# TMC2209_Camera_Slider_PCB.net
KiCad netlist of a schematic drawn in EAGLE
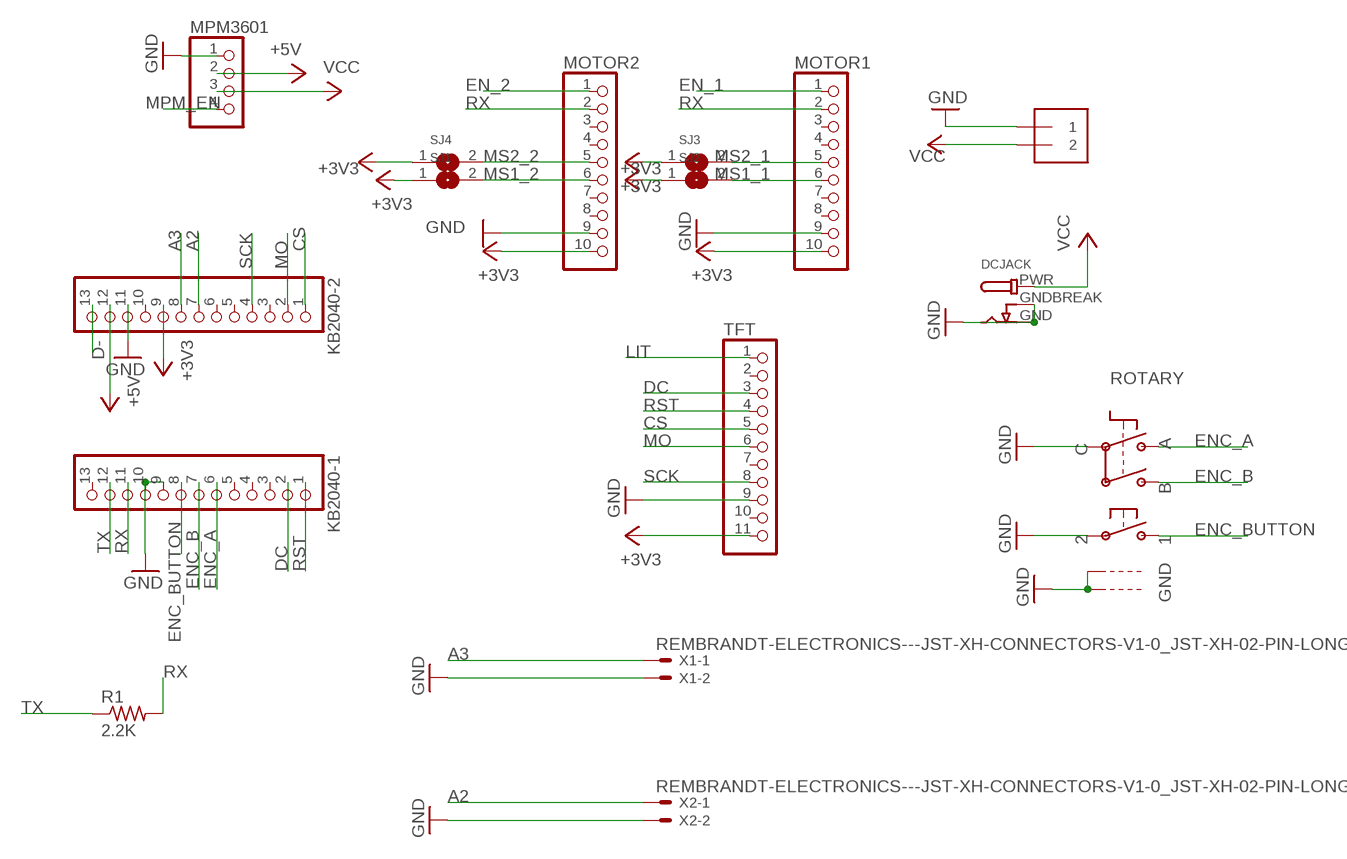
[diagram p0: schematic, sheet 1]

(export (version "E")
  (design (tool "Eeschema 10.0.6"))
  (components
    (comp (ref "DCJACK")
      (value "DCBARRELPTH")
      (footprint "eagle-import:DCJACK_2MM_PTH")
      (libsource (lib "eagle-import") (part "DCBARRELPTH"))
    )
    (comp (ref "J1")
      (value "1X2-3.5MM")
      (footprint "eagle-import:1X2-3.5MM")
      (libsource (lib "eagle-import") (part "1X2-3.5MM"))
    )
    (comp (ref "KB2040-1")
      (value "HEADER-1X13")
      (footprint "eagle-import:1X13_ROUND_70")
      (libsource (lib "eagle-import") (part "HEADER-1X13"))
    )
    (comp (ref "KB2040-2")
      (value "HEADER-1X13")
      (footprint "eagle-import:1X13_ROUND_70")
      (libsource (lib "eagle-import") (part "HEADER-1X13"))
    )
    (comp (ref "MOTOR1")
      (value "HEADER-1X10")
      (footprint "eagle-import:1X10_OVAL")
      (libsource (lib "eagle-import") (part "HEADER-1X10"))
    )
    (comp (ref "MOTOR2")
      (value "HEADER-1X10")
      (footprint "eagle-import:1X10_OVAL")
      (libsource (lib "eagle-import") (part "HEADER-1X10"))
    )
    (comp (ref "MPM3601")
      (value "HEADER-1X4")
      (footprint "eagle-import:1X04_OVAL")
      (libsource (lib "eagle-import") (part "HEADER-1X4"))
    )
    (comp (ref "R1")
      (value "2.2K")
      (footprint "eagle-import:0309_12")
      (libsource (lib "eagle-import") (part "R-US_0309/12"))
    )
    (comp (ref "ROTARY")
      (value "ENCODER_PLUS_SWITCH_BOURNS_PEC11")
      (footprint "eagle-import:PEC11+SWITCH")
      (libsource (lib "eagle-import") (part "ENCODER_PLUS_SWITCH_PEC11_BOURNS"))
    )
    (comp (ref "SJ1")
      (value "SOLDERJUMPERCLOSED")
      (footprint "eagle-import:SOLDERJUMPER_CLOSEDWIRE")
      (libsource (lib "eagle-import") (part "SOLDERJUMPERCLOSED"))
    )
    (comp (ref "SJ2")
      (value "SOLDERJUMPERREFLOW")
      (footprint "eagle-import:SOLDERJUMPER_REFLOW")
      (libsource (lib "eagle-import") (part "SOLDERJUMPERREFLOW"))
    )
    (comp (ref "SJ3")
      (value "SOLDERJUMPERREFLOW")
      (footprint "eagle-import:SOLDERJUMPER_REFLOW")
      (libsource (lib "eagle-import") (part "SOLDERJUMPERREFLOW"))
    )
    (comp (ref "SJ4")
      (value "SOLDERJUMPERREFLOW")
      (footprint "eagle-import:SOLDERJUMPER_REFLOW")
      (libsource (lib "eagle-import") (part "SOLDERJUMPERREFLOW"))
    )
    (comp (ref "TFT")
      (value "HEADER-1X11")
      (footprint "eagle-import:1X11_ROUND")
      (libsource (lib "eagle-import") (part "HEADER-1X11"))
    )
    (comp (ref "X1")
      (value "REMBRANDT-ELECTRONICS---JST-XH-CONNECTORS-V1-0_JST-XH-02-PIN-LONG-PAD")
      (footprint "eagle-import:REMBRANDT-ELECTRONICS---JST-XH-CONNECTORS-V1-0_JST-XH-02-PACKAGE-LONG-PAD")
      (libsource (lib "eagle-import") (part "REMBRANDT-ELECTRONICS---JST-XH-CONNECTORS-V1-0_JST-XH-02-PIN-LONG-PAD"))
    )
    (comp (ref "X2")
      (value "REMBRANDT-ELECTRONICS---JST-XH-CONNECTORS-V1-0_JST-XH-02-PIN-LONG-PAD")
      (footprint "eagle-import:REMBRANDT-ELECTRONICS---JST-XH-CONNECTORS-V1-0_JST-XH-02-PACKAGE-LONG-PAD")
      (libsource (lib "eagle-import") (part "REMBRANDT-ELECTRONICS---JST-XH-CONNECTORS-V1-0_JST-XH-02-PIN-LONG-PAD"))
    )
  )
  (nets
    (net (code "1") (name "+3V3") (class "Default")
      (node (ref "KB2040-2") (pin "9") (pinfunction "9_9") (pintype "passive"))
      (node (ref "MOTOR1") (pin "10") (pinfunction "10_10") (pintype "passive"))
      (node (ref "MOTOR2") (pin "10") (pinfunction "10_10") (pintype "passive"))
      (node (ref "SJ1") (pin "1") (pinfunction "1_1") (pintype "passive"))
      (node (ref "SJ2") (pin "1") (pinfunction "1_1") (pintype "passive"))
      (node (ref "SJ3") (pin "1") (pinfunction "1_1") (pintype "passive"))
      (node (ref "SJ4") (pin "1") (pinfunction "1_1") (pintype "passive"))
      (node (ref "TFT") (pin "11") (pinfunction "11_11") (pintype "passive"))
    )
    (net (code "2") (name "+5V") (class "Default")
      (node (ref "KB2040-2") (pin "12") (pinfunction "12_12") (pintype "passive"))
      (node (ref "MPM3601") (pin "2") (pinfunction "2_2") (pintype "passive"))
    )
    (net (code "3") (name "/A2") (class "Default")
      (node (ref "KB2040-2") (pin "7") (pinfunction "7_7") (pintype "passive"))
      (node (ref "X2") (pin "1") (pinfunction "S_1") (pintype "passive"))
    )
    (net (code "4") (name "/A3") (class "Default")
      (node (ref "KB2040-2") (pin "8") (pinfunction "8_8") (pintype "passive"))
      (node (ref "X1") (pin "1") (pinfunction "S_1") (pintype "passive"))
    )
    (net (code "5") (name "/CS") (class "Default")
      (node (ref "KB2040-2") (pin "1") (pinfunction "1_1") (pintype "passive"))
      (node (ref "TFT") (pin "5") (pinfunction "5_5") (pintype "passive"))
    )
    (net (code "6") (name "/D-") (class "Default")
      (node (ref "KB2040-2") (pin "13") (pinfunction "13_13") (pintype "passive"))
    )
    (net (code "7") (name "/DC") (class "Default")
      (node (ref "KB2040-1") (pin "2") (pinfunction "2_2") (pintype "passive"))
      (node (ref "TFT") (pin "3") (pinfunction "3_3") (pintype "passive"))
    )
    (net (code "8") (name "/ENC_A") (class "Default")
      (node (ref "KB2040-1") (pin "6") (pinfunction "6_6") (pintype "passive"))
      (node (ref "ROTARY") (pin "P$A") (pinfunction "P$A_P$A") (pintype "passive"))
    )
    (net (code "9") (name "/ENC_B") (class "Default")
      (node (ref "KB2040-1") (pin "7") (pinfunction "7_7") (pintype "passive"))
      (node (ref "ROTARY") (pin "P$B") (pinfunction "P$B_P$B") (pintype "passive"))
    )
    (net (code "10") (name "/ENC_BUTTON") (class "Default")
      (node (ref "KB2040-1") (pin "8") (pinfunction "8_8") (pintype "passive"))
      (node (ref "ROTARY") (pin "P$1") (pinfunction "P$1_P$1") (pintype "passive"))
    )
    (net (code "11") (name "/EN_1") (class "Default")
      (node (ref "MOTOR1") (pin "1") (pinfunction "1_1") (pintype "passive"))
    )
    (net (code "12") (name "/EN_2") (class "Default")
      (node (ref "MOTOR2") (pin "1") (pinfunction "1_1") (pintype "passive"))
    )
    (net (code "13") (name "/LIT") (class "Default")
      (node (ref "TFT") (pin "1") (pinfunction "1_1") (pintype "passive"))
    )
    (net (code "14") (name "/MO") (class "Default")
      (node (ref "KB2040-2") (pin "2") (pinfunction "2_2") (pintype "passive"))
      (node (ref "TFT") (pin "6") (pinfunction "6_6") (pintype "passive"))
    )
    (net (code "15") (name "/MPM_EN") (class "Default")
      (node (ref "MPM3601") (pin "4") (pinfunction "4_4") (pintype "passive"))
    )
    (net (code "16") (name "/MS1_1") (class "Default")
      (node (ref "MOTOR1") (pin "6") (pinfunction "6_6") (pintype "passive"))
      (node (ref "SJ2") (pin "2") (pinfunction "2_2") (pintype "passive"))
    )
    (net (code "17") (name "/MS1_2") (class "Default")
      (node (ref "MOTOR2") (pin "6") (pinfunction "6_6") (pintype "passive"))
      (node (ref "SJ1") (pin "2") (pinfunction "2_2") (pintype "passive"))
    )
    (net (code "18") (name "/MS2_1") (class "Default")
      (node (ref "MOTOR1") (pin "5") (pinfunction "5_5") (pintype "passive"))
      (node (ref "SJ3") (pin "2") (pinfunction "2_2") (pintype "passive"))
    )
    (net (code "19") (name "/MS2_2") (class "Default")
      (node (ref "MOTOR2") (pin "5") (pinfunction "5_5") (pintype "passive"))
      (node (ref "SJ4") (pin "2") (pinfunction "2_2") (pintype "passive"))
    )
    (net (code "20") (name "/RST") (class "Default")
      (node (ref "KB2040-1") (pin "1") (pinfunction "1_1") (pintype "passive"))
      (node (ref "TFT") (pin "4") (pinfunction "4_4") (pintype "passive"))
    )
    (net (code "21") (name "/RX") (class "Default")
      (node (ref "KB2040-1") (pin "11") (pinfunction "11_11") (pintype "passive"))
      (node (ref "MOTOR1") (pin "2") (pinfunction "2_2") (pintype "passive"))
      (node (ref "MOTOR2") (pin "2") (pinfunction "2_2") (pintype "passive"))
      (node (ref "R1") (pin "2") (pinfunction "2_2") (pintype "passive"))
    )
    (net (code "22") (name "/SCK") (class "Default")
      (node (ref "KB2040-2") (pin "4") (pinfunction "4_4") (pintype "passive"))
      (node (ref "TFT") (pin "8") (pinfunction "8_8") (pintype "passive"))
    )
    (net (code "23") (name "/TX") (class "Default")
      (node (ref "KB2040-1") (pin "12") (pinfunction "12_12") (pintype "passive"))
      (node (ref "R1") (pin "1") (pinfunction "1_1") (pintype "passive"))
    )
    (net (code "24") (name "GND") (class "Default")
      (node (ref "DCJACK") (pin "GND") (pinfunction "GND_GND") (pintype "power_in"))
      (node (ref "DCJACK") (pin "GNDBREAK") (pinfunction "GNDBREAK_GNDBREAK") (pintype "power_in"))
      (node (ref "J1") (pin "1") (pinfunction "1_1") (pintype "passive"))
      (node (ref "KB2040-1") (pin "10") (pinfunction "10_10") (pintype "passive"))
      (node (ref "KB2040-1") (pin "9") (pinfunction "9_9") (pintype "passive"))
      (node (ref "KB2040-2") (pin "11") (pinfunction "11_11") (pintype "passive"))
      (node (ref "MOTOR1") (pin "9") (pinfunction "9_9") (pintype "passive"))
      (node (ref "MOTOR2") (pin "9") (pinfunction "9_9") (pintype "passive"))
      (node (ref "MPM3601") (pin "1") (pinfunction "1_1") (pintype "passive"))
      (node (ref "ROTARY") (pin "P$2") (pinfunction "P$2_P$2") (pintype "passive"))
      (node (ref "ROTARY") (pin "P$C") (pinfunction "P$C_P$C") (pintype "passive"))
      (node (ref "ROTARY") (pin "P$GND1") (pinfunction "P$GND1_P$GND1") (pintype "passive"))
      (node (ref "ROTARY") (pin "P$GND2") (pinfunction "P$GND2_P$GND2") (pintype "passive"))
      (node (ref "TFT") (pin "9") (pinfunction "9_9") (pintype "passive"))
      (node (ref "X1") (pin "2") (pinfunction "S_2") (pintype "passive"))
      (node (ref "X2") (pin "2") (pinfunction "S_2") (pintype "passive"))
    )
    (net (code "25") (name "VCC") (class "Default")
      (node (ref "DCJACK") (pin "PWR") (pinfunction "PWR_PWR") (pintype "power_in"))
      (node (ref "J1") (pin "2") (pinfunction "2_2") (pintype "passive"))
      (node (ref "MPM3601") (pin "3") (pinfunction "3_3") (pintype "passive"))
    )
    (net (code "26") (name "unconnected-(KB2040-1-Pad3)") (class "Default")
      (node (ref "KB2040-1") (pin "3") (pinfunction "3_3") (pintype "passive"))
    )
    (net (code "27") (name "unconnected-(KB2040-1-Pad4)") (class "Default")
      (node (ref "KB2040-1") (pin "4") (pinfunction "4_4") (pintype "passive"))
    )
    (net (code "28") (name "unconnected-(KB2040-1-Pad5)") (class "Default")
      (node (ref "KB2040-1") (pin "5") (pinfunction "5_5") (pintype "passive"))
    )
    (net (code "29") (name "unconnected-(KB2040-1-Pad13)") (class "Default")
      (node (ref "KB2040-1") (pin "13") (pinfunction "13_13") (pintype "passive"))
    )
    (net (code "30") (name "unconnected-(KB2040-2-Pad3)") (class "Default")
      (node (ref "KB2040-2") (pin "3") (pinfunction "3_3") (pintype "passive"))
    )
    (net (code "31") (name "unconnected-(KB2040-2-Pad5)") (class "Default")
      (node (ref "KB2040-2") (pin "5") (pinfunction "5_5") (pintype "passive"))
    )
    (net (code "32") (name "unconnected-(KB2040-2-Pad6)") (class "Default")
      (node (ref "KB2040-2") (pin "6") (pinfunction "6_6") (pintype "passive"))
    )
    (net (code "33") (name "unconnected-(KB2040-2-Pad10)") (class "Default")
      (node (ref "KB2040-2") (pin "10") (pinfunction "10_10") (pintype "passive"))
    )
    (net (code "34") (name "unconnected-(MOTOR1-Pad3)") (class "Default")
      (node (ref "MOTOR1") (pin "3") (pinfunction "3_3") (pintype "passive"))
    )
    (net (code "35") (name "unconnected-(MOTOR1-Pad4)") (class "Default")
      (node (ref "MOTOR1") (pin "4") (pinfunction "4_4") (pintype "passive"))
    )
    (net (code "36") (name "unconnected-(MOTOR1-Pad7)") (class "Default")
      (node (ref "MOTOR1") (pin "7") (pinfunction "7_7") (pintype "passive"))
    )
    (net (code "37") (name "unconnected-(MOTOR1-Pad8)") (class "Default")
      (node (ref "MOTOR1") (pin "8") (pinfunction "8_8") (pintype "passive"))
    )
    (net (code "38") (name "unconnected-(MOTOR2-Pad3)") (class "Default")
      (node (ref "MOTOR2") (pin "3") (pinfunction "3_3") (pintype "passive"))
    )
    (net (code "39") (name "unconnected-(MOTOR2-Pad4)") (class "Default")
      (node (ref "MOTOR2") (pin "4") (pinfunction "4_4") (pintype "passive"))
    )
    (net (code "40") (name "unconnected-(MOTOR2-Pad7)") (class "Default")
      (node (ref "MOTOR2") (pin "7") (pinfunction "7_7") (pintype "passive"))
    )
    (net (code "41") (name "unconnected-(MOTOR2-Pad8)") (class "Default")
      (node (ref "MOTOR2") (pin "8") (pinfunction "8_8") (pintype "passive"))
    )
    (net (code "42") (name "unconnected-(TFT-Pad2)") (class "Default")
      (node (ref "TFT") (pin "2") (pinfunction "2_2") (pintype "passive"))
    )
    (net (code "43") (name "unconnected-(TFT-Pad7)") (class "Default")
      (node (ref "TFT") (pin "7") (pinfunction "7_7") (pintype "passive"))
    )
    (net (code "44") (name "unconnected-(TFT-Pad10)") (class "Default")
      (node (ref "TFT") (pin "10") (pinfunction "10_10") (pintype "passive"))
    )
  )
)
